# air_qulity_monitor.net
KiCad netlist of a schematic drawn in Altium Designer
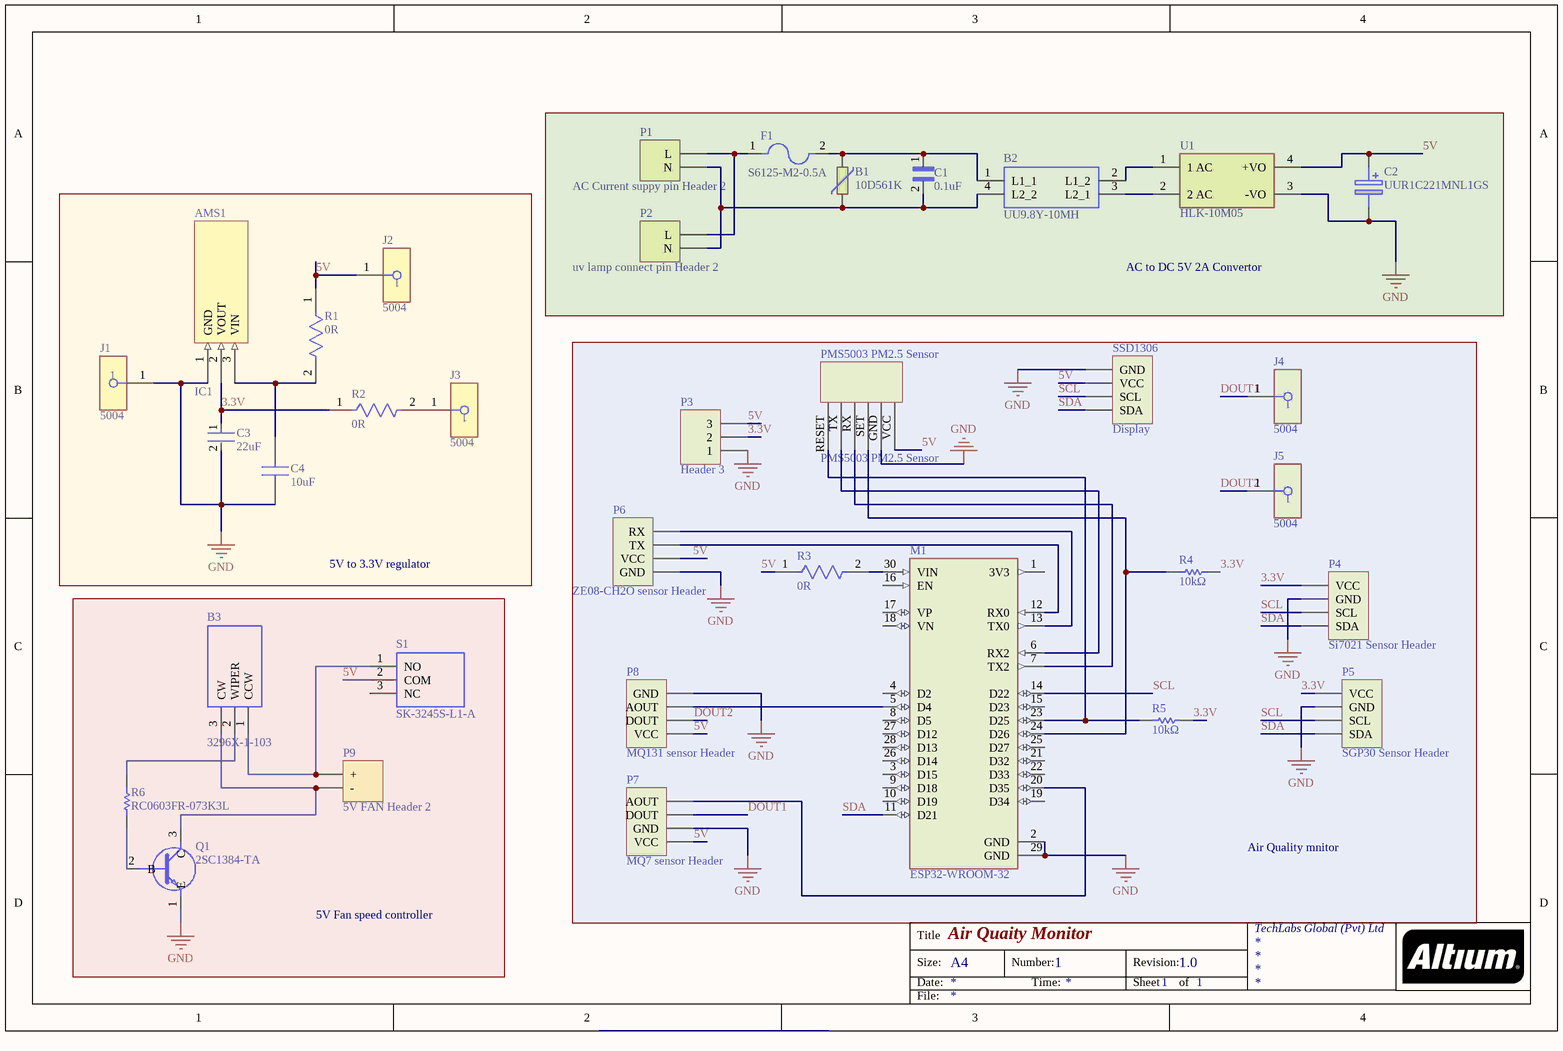
[diagram p0: air qulity monitor.SchDoc]

(export (version "E")
  (design (tool "Eeschema 10.0.6"))
  (components
    (comp (ref "AMS1")
      (value "IC1")
      (footprint "SOT89-150P350X150-3N")
      (fields
        (field (name "MANUFACTURER") "YONGYUTAI")
        (field (name "MFR. PART #") "AMS1117-3.3")
        (field (name "LCSC PART #") "C2904742")
      )
      (libsource (lib "AMS1117-3.3") (part "IC?"))
    )
    (comp (ref "B1")
      (value "10D561K")
      (footprint "10D561K")
      (description "920V 42.3J 180pF@1kHz 460V 350V 504V~616V 2.5kA Plugin Varistors ROHS")
      (fields (field (name "LCSC PART #") "C113236") (field (name "MANUFACTURER") "Hongzhi Elec"))
      (libsource (lib "10D561K") (part "10D561K"))
    )
    (comp (ref "B2")
      (value "UU9.8Y-10MH")
      (footprint "UU98Y10MH")
      (description "Common Mode Chokes / Filters Power Line 10mH @ 1kHz 500mA Through Hole RoHS")
      (libsource (lib "UU9.8Y-10MH") (part "UU9.8Y-10MH"))
    )
    (comp (ref "B3")
      (value "3296X-1-103")
      (footprint "3296X1223LF")
      (description "3296X side adj cermet trimmer,10K 10mm")
      (fields (field (name "MOUSER PART NUMBER") "652-3296X-1-103"))
      (libsource (lib "3296X-1-103") (part "3296X-1-103"))
    )
    (comp (ref "C1")
      (value "0.1uF")
      (footprint "MPX-104K275VAC-C-D2")
      (description "0.1uF ±10% -40℃~+110℃ X2 275VAC Radial Leaded,P=15mm Suppression Capacitors ROHS")
      (fields (field (name "LCSC PART #") "C3249976") (field (name "MANUFACTURER") "CORETONG"))
      (libsource (lib "MPX-104K275VAC-C-D2") (part "MPX-104K275VAC-C-D2"))
    )
    (comp (ref "C2")
      (value "UUR1C221MNL1GS")
      (footprint "CAPAE830X1050N")
      (description "Nichicon 220uF 16V dc Aluminium Electrolytic Capacitor, Surface Mount 8 (Dia.) x 10mm +85C 8mm")
      (fields (field (name "MOUSER PART NUMBER") "647-UUR1C221MNL1GS"))
      (libsource (lib "UUR1C221MNL1GS") (part "UUR1C221MNL1GS"))
    )
    (comp (ref "C3")
      (value "22uF")
      (footprint "FP-GRM219-0_2-0_15-IPC_A")
      (description "Chip Multilayer Ceramic Capacitors for General Purpose, 0805, 22uF, X5R, 15%, 20%, 16V")
      (fields (field (name "MFR. PART #") "GRM219R61C226ME15L") (field (name "LCSC PART #") "C162295"))
      (libsource (lib "Altium Content Vault") (part "b4654b650e69147ec39a6b967a45e02"))
    )
    (comp (ref "C4")
      (value "10uF")
      (footprint "CAPC1005X70N")
      (description "6.3V 10uF X5R ±20% 0402 Multilayer Ceramic Capacitors MLCC - SMD/SMT ROHS")
      (fields
        (field (name "MANUFACTURER") "Samsung Electro-Mechanics")
        (field (name "MFR. PART #") "CL05A106MQ5NUNC")
      )
      (libsource (lib "CL05A106MQ5NUNC") (part "CL05A106MQ5NUNC"))
    )
    (comp (ref "F1")
      (value "S6125-M2-0.5A")
      (footprint "CAPC6125X25N")
      (description "SMD Fuses ROHS")
      (fields (field (name "LCSC PART #") "C845172") (field (name "MANUFACTURER") "SART(Nanjing Sart Tech)"))
      (libsource (lib "S6125-M2-0.5A") (part "S6125-M2-0.5A"))
    )
    (comp (ref "J1")
      (value "5004")
      (footprint "FP-5004-MFG")
      (description "PC TEST POINT MINIATURE YELLOW")
      (fields (field (name "MANUFACTURER") "Keystone") (field (name "LCSC PART #") "C2906762"))
      (libsource (lib "") (part "98815daf2f2c152b0c43f5ab9800df6_1"))
    )
    (comp (ref "J2")
      (value "5004")
      (footprint "FP-5004-MFG")
      (description "PC TEST POINT MINIATURE YELLOW")
      (fields (field (name "MANUFACTURER") "Keystone") (field (name "LCSC PART #") "C2906762"))
      (libsource (lib "Altium Content Vault") (part "98815daf2f2c152b0c43f5ab9800df6"))
    )
    (comp (ref "J3")
      (value "5004")
      (footprint "FP-5004-MFG")
      (description "PC TEST POINT MINIATURE YELLOW")
      (fields (field (name "MANUFACTURER") "Keystone") (field (name "LCSC PART #") "C2906762"))
      (libsource (lib "Altium Content Vault") (part "98815daf2f2c152b0c43f5ab9800df6"))
    )
    (comp (ref "J4")
      (value "5004")
      (footprint "FP-5004-MFG")
      (description "PC TEST POINT MINIATURE YELLOW")
      (fields (field (name "MANUFACTURER") "Keystone") (field (name "LCSC PART #") "C2906762"))
      (libsource (lib "Altium Content Vault") (part "98815daf2f2c152b0c43f5ab9800df6"))
    )
    (comp (ref "J5")
      (value "5004")
      (footprint "FP-5004-MFG")
      (description "PC TEST POINT MINIATURE YELLOW")
      (fields (field (name "MANUFACTURER") "Keystone") (field (name "LCSC PART #") "C2906762"))
      (libsource (lib "Altium Content Vault") (part "98815daf2f2c152b0c43f5ab9800df6"))
    )
    (comp (ref "M1")
      (value "ESP32-WROOM-32")
      (footprint "ESP32-DEVKIT-V1")
      (libsource (lib "Modules") (part "ESP32-DEVKIT-V1"))
    )
    (comp (ref "P1")
      (value "AC Current suppy pin Header 2")
      (footprint "HDR1X2")
      (description "Header, 2-Pin")
      (fields (field (name "PUBLISHER") "Altium Limited"))
      (libsource (lib "") (part "Header 2_1"))
    )
    (comp (ref "P2")
      (value "uv lamp connect pin Header 2")
      (footprint "HDR1X2")
      (description "Header, 2-Pin")
      (fields (field (name "PUBLISHER") "Altium Limited"))
      (libsource (lib "") (part "Header 2_1"))
    )
    (comp (ref "P3")
      (value "Header 3")
      (footprint "HDR1X3")
      (description "Header, 3-Pin")
      (fields (field (name "PUBLISHER") "Altium Limited"))
      (libsource (lib "Miscellaneous Connectors") (part "Header 3"))
    )
    (comp (ref "P4")
      (value "Si7021 Sensor Header")
      (footprint "HDR1X4")
      (description "Header, 4-Pin")
      (fields (field (name "PUBLISHER") "Altium Limited"))
      (libsource (lib "") (part "Header 4_2"))
    )
    (comp (ref "P5")
      (value "SGP30 Sensor Header")
      (footprint "HDR1X4")
      (description "Header, 4-Pin")
      (fields (field (name "PUBLISHER") "Altium Limited"))
      (libsource (lib "") (part "Header 4_2"))
    )
    (comp (ref "P6")
      (value "ZE08-CH2O sensor Header")
      (footprint "HDR1X4")
      (description "Header, 4-Pin")
      (fields (field (name "PUBLISHER") "Altium Limited"))
      (libsource (lib "Miscellaneous Connectors") (part "Header 4"))
    )
    (comp (ref "P7")
      (value "MQ7 sensor Header")
      (footprint "HDR1X4")
      (description "Header, 4-Pin")
      (fields (field (name "PUBLISHER") "Altium Limited"))
      (libsource (lib "Miscellaneous Connectors") (part "Header 4"))
    )
    (comp (ref "P8")
      (value "MQ131 sensor Header")
      (footprint "HDR1X4")
      (description "Header, 4-Pin")
      (fields (field (name "PUBLISHER") "Altium Limited"))
      (libsource (lib "Miscellaneous Connectors") (part "Header 4"))
    )
    (comp (ref "P9")
      (value "5V FAN Header 2")
      (footprint "HDR1X2")
      (description "Header, 2-Pin")
      (fields (field (name "PUBLISHER") "Altium Limited"))
      (libsource (lib "Miscellaneous Connectors") (part "Header 2"))
    )
    (comp (ref "PMS5003 PM2.5 Sensor")
      (value "PMS5003 PM2.5 Sensor")
      (footprint "PMS5003 PM2.5 Sensor")
      (libsource (lib "DIY Air Quality Monitor Library") (part "PMS5003 PM2.5 Sensor"))
    )
    (comp (ref "Q1")
      (value "2SC1384-TA")
      (footprint "2SC1384-TA")
      (description "Bipolar Transistors - BJT NPN Si Transistor Epitaxial")
      (fields
        (field (name "MANUFACTURER") "Jiangsu Changjing Electronics Technology Co., Ltd.")
        (field (name "LCSC PART #") "C2910422")
      )
      (libsource (lib "2SC1384-TA") (part "2SC1384-TA"))
    )
    (comp (ref "R1")
      (value "0R")
      (footprint "FP-RC0402-0_4-IPC_A")
      (description "RES SMD 0 OHM JUMPER 1/16W 0402")
      (fields (field (name "MANUFACTURER") "Yageo") (field (name "LCSC PART #") "C106231"))
      (libsource (lib "Altium Content Vault") (part "1029c3af85768c4190bb7ad29bc67b5"))
    )
    (comp (ref "R2")
      (value "0R")
      (footprint "FP-RC0402-0_4-IPC_A")
      (description "RES SMD 0 OHM JUMPER 1/16W 0402")
      (fields (field (name "MANUFACTURER") "Yageo") (field (name "LCSC PART #") "C106231"))
      (libsource (lib "Altium Content Vault") (part "1029c3af85768c4190bb7ad29bc67b5"))
    )
    (comp (ref "R3")
      (value "0R")
      (footprint "FP-RC0402-0_4-IPC_A")
      (description "RES SMD 0 OHM JUMPER 1/16W 0402")
      (fields (field (name "MANUFACTURER") "Yageo") (field (name "LCSC PART #") "C106231"))
      (libsource (lib "Altium Content Vault") (part "1029c3af85768c4190bb7ad29bc67b5"))
    )
    (comp (ref "R4")
      (value "10kΩ")
      (footprint "RESC1005X40X25LL05T10")
      (description "62.5mW 50V ±100ppm/℃ ±1% -55℃~+155℃ 10kΩ 0402 Chip Resistor - Surface Mount ROHS")
      (fields (field (name "MFR. PART #") "RC0402FR-0710KL") (field (name "MANUFACTURER") "Yageo / Phycomp"))
      (libsource (lib "Altium Content Vault") (part "RES"))
    )
    (comp (ref "R5")
      (value "10kΩ")
      (footprint "RESC1005X40X25LL05T10")
      (description "62.5mW 50V ±100ppm/℃ ±1% -55℃~+155℃ 10kΩ 0402 Chip Resistor - Surface Mount ROHS")
      (fields (field (name "MFR. PART #") "RC0402FR-0710KL") (field (name "MANUFACTURER") "Yageo / Phycomp"))
      (libsource (lib "Altium Content Vault") (part "RES"))
    )
    (comp (ref "R6")
      (value "RC0603FR-073K3L")
      (footprint "RESC1608X55X25ML10T15")
      (description "Chip Resistor, 3.3 KOhm, +/- 1%, 0.1 W, -55 to 155 degC, 0603 (1608 Metric), RoHS, Tape and Reel")
      (fields (field (name "MANUFACTURER") "Yageo") (field (name "TOLERANCE") "1%"))
      (libsource (lib "Altium Content Vault") (part "RES-2"))
    )
    (comp (ref "S1")
      (value "SK-3245S-L1-A")
      (footprint "SK3245SL1A")
      (libsource (lib "SK-3245S-L1-A") (part "SK-3245S-L1-A"))
    )
    (comp (ref "SSD1306")
      (value "Display")
      (footprint "HDR1X4")
      (description "Header, 4-Pin")
      (fields (field (name "PUBLISHER") "Altium Limited"))
      (libsource (lib "") (part "Header 4_1"))
    )
    (comp (ref "U1")
      (value "HLK-10M05")
      (footprint "FP-HLK-10M05-MFG")
      (description "10W Ultra-Compact Power Module")
      (libsource (lib "Altium Content Vault") (part "a65b17ccb3a75dffb3c3e849074403b"))
    )
  )
  (nets
    (net (code "1") (name "/3.3V") (class "Default")
      (node (ref "AMS1") (pin "2") (pinfunction "VOUT_2") (pintype "input"))
      (node (ref "C3") (pin "1") (pinfunction "1_1") (pintype "passive"))
      (node (ref "P3") (pin "2") (pinfunction "2_2") (pintype "passive"))
      (node (ref "P4") (pin "1") (pinfunction "VCC_1") (pintype "passive"))
      (node (ref "P5") (pin "1") (pinfunction "VCC_1") (pintype "passive"))
      (node (ref "R2") (pin "1") (pinfunction "1_1") (pintype "passive"))
      (node (ref "R4") (pin "2") (pinfunction "2_2") (pintype "passive"))
      (node (ref "R5") (pin "2") (pinfunction "2_2") (pintype "passive"))
    )
    (net (code "2") (name "/5V") (class "Default")
      (node (ref "C2") (pin "1") (pinfunction "+_1") (pintype "passive"))
      (node (ref "J2") (pin "1") (pinfunction "1_1") (pintype "passive"))
      (node (ref "P3") (pin "3") (pinfunction "3_3") (pintype "passive"))
      (node (ref "P6") (pin "2") (pinfunction "VCC_2") (pintype "passive"))
      (node (ref "P7") (pin "1") (pinfunction "GND_1") (pintype "passive"))
      (node (ref "P8") (pin "1") (pinfunction "GND_1") (pintype "passive"))
      (node (ref "PMS5003 PM2.5 Sensor") (pin "VCC") (pintype "passive"))
      (node (ref "R1") (pin "1") (pinfunction "1_1") (pintype "passive"))
      (node (ref "R3") (pin "1") (pinfunction "1_1") (pintype "passive"))
      (node (ref "S1") (pin "2") (pinfunction "COM_2") (pintype "passive"))
      (node (ref "SSD1306") (pin "2") (pinfunction "VCC_2") (pintype "passive"))
      (node (ref "U1") (pin "4") (pinfunction "+VO_4") (pintype "power_in"))
    )
    (net (code "3") (name "/DOUT1") (class "Default")
      (node (ref "J4") (pin "1") (pinfunction "1_1") (pintype "passive"))
      (node (ref "P7") (pin "3") (pinfunction "TX_3") (pintype "passive"))
    )
    (net (code "4") (name "/DOUT2") (class "Default")
      (node (ref "J5") (pin "1") (pinfunction "1_1") (pintype "passive"))
      (node (ref "P8") (pin "2") (pinfunction "VCC_2") (pintype "passive"))
    )
    (net (code "5") (name "/SCL") (class "Default")
      (node (ref "M1") (pin "14") (pinfunction "D22_14") (pintype "bidirectional"))
      (node (ref "P4") (pin "3") (pinfunction "SCL_3") (pintype "passive"))
      (node (ref "P5") (pin "3") (pinfunction "SCL_3") (pintype "passive"))
      (node (ref "SSD1306") (pin "3") (pinfunction "SCL_3") (pintype "passive"))
    )
    (net (code "6") (name "/SDA") (class "Default")
      (node (ref "M1") (pin "11") (pinfunction "D21_11") (pintype "bidirectional"))
      (node (ref "P4") (pin "4") (pinfunction "SDA_4") (pintype "passive"))
      (node (ref "P5") (pin "4") (pinfunction "SDA_4") (pintype "passive"))
      (node (ref "SSD1306") (pin "4") (pinfunction "SDA_4") (pintype "passive"))
    )
    (net (code "7") (name "GND") (class "Default")
      (node (ref "AMS1") (pin "1") (pinfunction "GND_1") (pintype "input"))
      (node (ref "C2") (pin "2") (pinfunction "-_2") (pintype "passive"))
      (node (ref "C3") (pin "2") (pinfunction "2_2") (pintype "passive"))
      (node (ref "C4") (pin "1") (pinfunction "1_1") (pintype "passive"))
      (node (ref "J1") (pin "1") (pinfunction "1_1") (pintype "passive"))
      (node (ref "M1") (pin "2") (pinfunction "GND_2") (pintype "power_in"))
      (node (ref "M1") (pin "29") (pinfunction "GND_29") (pintype "power_in"))
      (node (ref "P3") (pin "1") (pinfunction "1_1") (pintype "passive"))
      (node (ref "P4") (pin "2") (pinfunction "GND_2") (pintype "passive"))
      (node (ref "P5") (pin "2") (pinfunction "GND_2") (pintype "passive"))
      (node (ref "P6") (pin "1") (pinfunction "GND_1") (pintype "passive"))
      (node (ref "P7") (pin "2") (pinfunction "VCC_2") (pintype "passive"))
      (node (ref "P8") (pin "4") (pinfunction "RX_4") (pintype "passive"))
      (node (ref "PMS5003 PM2.5 Sensor") (pin "GND") (pintype "passive"))
      (node (ref "Q1") (pin "1") (pinfunction "E_1") (pintype "passive"))
      (node (ref "SSD1306") (pin "1") (pinfunction "GND_1") (pintype "passive"))
      (node (ref "U1") (pin "3") (pinfunction "-VO_3") (pintype "power_in"))
    )
    (net (code "8") (name "Net-(AMS1-VIN)") (class "Default")
      (node (ref "AMS1") (pin "3") (pinfunction "VIN_3") (pintype "input"))
      (node (ref "C4") (pin "2") (pinfunction "2_2") (pintype "passive"))
      (node (ref "R1") (pin "2") (pinfunction "2_2") (pintype "passive"))
    )
    (net (code "9") (name "Net-(B2-L1_1)") (class "Default")
      (node (ref "B1") (pin "1") (pinfunction "1_1") (pintype "passive"))
      (node (ref "B2") (pin "1") (pinfunction "L1_1_1") (pintype "passive"))
      (node (ref "C1") (pin "1") (pinfunction "1_1") (pintype "passive"))
      (node (ref "F1") (pin "2") (pinfunction "2_2") (pintype "passive"))
    )
    (net (code "10") (name "Net-(B2-L1_2)") (class "Default")
      (node (ref "B2") (pin "2") (pinfunction "L1_2_2") (pintype "passive"))
      (node (ref "U1") (pin "1") (pinfunction "1_AC_1") (pintype "passive"))
    )
    (net (code "11") (name "Net-(B2-L2_1)") (class "Default")
      (node (ref "B2") (pin "3") (pinfunction "L2_1_3") (pintype "passive"))
      (node (ref "U1") (pin "2") (pinfunction "2_AC_2") (pintype "passive"))
    )
    (net (code "12") (name "Net-(B2-L2_2)") (class "Default")
      (node (ref "B1") (pin "2") (pinfunction "2_2") (pintype "passive"))
      (node (ref "B2") (pin "4") (pinfunction "L2_2_4") (pintype "passive"))
      (node (ref "C1") (pin "2") (pinfunction "2_2") (pintype "passive"))
      (node (ref "P1") (pin "1") (pinfunction "N_1") (pintype "passive"))
      (node (ref "P2") (pin "1") (pinfunction "N_1") (pintype "passive"))
    )
    (net (code "13") (name "Net-(B3-CCW)") (class "Default")
      (node (ref "B3") (pin "1") (pinfunction "CCW_1") (pintype "passive"))
      (node (ref "P9") (pin "1") (pinfunction "+_1") (pintype "passive"))
      (node (ref "S1") (pin "1") (pinfunction "NO_1") (pintype "passive"))
    )
    (net (code "14") (name "Net-(B3-CW)") (class "Default")
      (node (ref "B3") (pin "3") (pinfunction "CW_3") (pintype "passive"))
      (node (ref "P9") (pin "2") (pinfunction "-_2") (pintype "passive"))
      (node (ref "Q1") (pin "3") (pinfunction "C_3") (pintype "passive"))
    )
    (net (code "15") (name "Net-(B3-WIPER)") (class "Default")
      (node (ref "B3") (pin "2") (pinfunction "WIPER_2") (pintype "passive"))
      (node (ref "R6") (pin "2") (pinfunction "2_2") (pintype "passive"))
    )
    (net (code "16") (name "Net-(J3-Pad1)") (class "Default")
      (node (ref "J3") (pin "1") (pinfunction "1_1") (pintype "passive"))
      (node (ref "R2") (pin "2") (pinfunction "2_2") (pintype "passive"))
    )
    (net (code "17") (name "Net-(M1-D4)") (class "Default")
      (node (ref "M1") (pin "5") (pinfunction "D4_5") (pintype "bidirectional"))
      (node (ref "P8") (pin "3") (pinfunction "TX_3") (pintype "passive"))
    )
    (net (code "18") (name "Net-(M1-D25)") (class "Default")
      (node (ref "M1") (pin "23") (pinfunction "D25_23") (pintype "bidirectional"))
      (node (ref "PMS5003 PM2.5 Sensor") (pin "RESET") (pintype "passive"))
      (node (ref "R5") (pin "1") (pinfunction "1_1") (pintype "passive"))
    )
    (net (code "19") (name "Net-(M1-D26)") (class "Default")
      (node (ref "M1") (pin "24") (pinfunction "D26_24") (pintype "bidirectional"))
      (node (ref "PMS5003 PM2.5 Sensor") (pin "SET") (pintype "passive"))
      (node (ref "R4") (pin "1") (pinfunction "1_1") (pintype "passive"))
    )
    (net (code "20") (name "Net-(M1-D35)") (class "Default")
      (node (ref "M1") (pin "20") (pinfunction "D35_20") (pintype "bidirectional"))
      (node (ref "P7") (pin "4") (pinfunction "RX_4") (pintype "passive"))
    )
    (net (code "21") (name "Net-(M1-RX0)") (class "Default")
      (node (ref "M1") (pin "12") (pinfunction "RX0_12") (pintype "input"))
      (node (ref "P6") (pin "3") (pinfunction "TX_3") (pintype "passive"))
    )
    (net (code "22") (name "Net-(M1-RX2)") (class "Default")
      (node (ref "M1") (pin "6") (pinfunction "RX2_6") (pintype "input"))
      (node (ref "PMS5003 PM2.5 Sensor") (pin "TX") (pintype "passive"))
    )
    (net (code "23") (name "Net-(M1-TX0)") (class "Default")
      (node (ref "M1") (pin "13") (pinfunction "TX0_13") (pintype "output"))
      (node (ref "P6") (pin "4") (pinfunction "RX_4") (pintype "passive"))
    )
    (net (code "24") (name "Net-(M1-TX2)") (class "Default")
      (node (ref "M1") (pin "7") (pinfunction "TX2_7") (pintype "output"))
      (node (ref "PMS5003 PM2.5 Sensor") (pin "RX") (pintype "passive"))
    )
    (net (code "25") (name "Net-(M1-VIN)") (class "Default")
      (node (ref "M1") (pin "30") (pinfunction "VIN_30") (pintype "input"))
      (node (ref "R3") (pin "2") (pinfunction "2_2") (pintype "passive"))
    )
    (net (code "26") (name "Net-(P1-L)") (class "Default")
      (node (ref "F1") (pin "1") (pinfunction "1_1") (pintype "passive"))
      (node (ref "P1") (pin "2") (pinfunction "L_2") (pintype "passive"))
      (node (ref "P2") (pin "2") (pinfunction "L_2") (pintype "passive"))
    )
    (net (code "27") (name "Net-(Q1-B)") (class "Default")
      (node (ref "Q1") (pin "2") (pinfunction "B_2") (pintype "passive"))
      (node (ref "R6") (pin "1") (pinfunction "1_1") (pintype "passive"))
    )
    (net (code "28") (name "unconnected-(M1-3V3-Pad1)") (class "Default")
      (node (ref "M1") (pin "1") (pinfunction "3V3_1") (pintype "output"))
    )
    (net (code "29") (name "unconnected-(M1-D2-Pad4)") (class "Default")
      (node (ref "M1") (pin "4") (pinfunction "D2_4") (pintype "bidirectional"))
    )
    (net (code "30") (name "unconnected-(M1-D5-Pad8)") (class "Default")
      (node (ref "M1") (pin "8") (pinfunction "D5_8") (pintype "bidirectional"))
    )
    (net (code "31") (name "unconnected-(M1-D12-Pad27)") (class "Default")
      (node (ref "M1") (pin "27") (pinfunction "D12_27") (pintype "bidirectional"))
    )
    (net (code "32") (name "unconnected-(M1-D13-Pad28)") (class "Default")
      (node (ref "M1") (pin "28") (pinfunction "D13_28") (pintype "bidirectional"))
    )
    (net (code "33") (name "unconnected-(M1-D14-Pad26)") (class "Default")
      (node (ref "M1") (pin "26") (pinfunction "D14_26") (pintype "bidirectional"))
    )
    (net (code "34") (name "unconnected-(M1-D15-Pad3)") (class "Default")
      (node (ref "M1") (pin "3") (pinfunction "D15_3") (pintype "bidirectional"))
    )
    (net (code "35") (name "unconnected-(M1-D18-Pad9)") (class "Default")
      (node (ref "M1") (pin "9") (pinfunction "D18_9") (pintype "bidirectional"))
    )
    (net (code "36") (name "unconnected-(M1-D19-Pad10)") (class "Default")
      (node (ref "M1") (pin "10") (pinfunction "D19_10") (pintype "bidirectional"))
    )
    (net (code "37") (name "unconnected-(M1-D23-Pad15)") (class "Default")
      (node (ref "M1") (pin "15") (pinfunction "D23_15") (pintype "bidirectional"))
    )
    (net (code "38") (name "unconnected-(M1-D27-Pad25)") (class "Default")
      (node (ref "M1") (pin "25") (pinfunction "D27_25") (pintype "bidirectional"))
    )
    (net (code "39") (name "unconnected-(M1-D32-Pad21)") (class "Default")
      (node (ref "M1") (pin "21") (pinfunction "D32_21") (pintype "bidirectional"))
    )
    (net (code "40") (name "unconnected-(M1-D33-Pad22)") (class "Default")
      (node (ref "M1") (pin "22") (pinfunction "D33_22") (pintype "bidirectional"))
    )
    (net (code "41") (name "unconnected-(M1-D34-Pad19)") (class "Default")
      (node (ref "M1") (pin "19") (pinfunction "D34_19") (pintype "bidirectional"))
    )
    (net (code "42") (name "unconnected-(M1-EN-Pad16)") (class "Default")
      (node (ref "M1") (pin "16") (pinfunction "EN_16") (pintype "input"))
    )
    (net (code "43") (name "unconnected-(M1-VN-Pad18)") (class "Default")
      (node (ref "M1") (pin "18") (pinfunction "VN_18") (pintype "bidirectional"))
    )
    (net (code "44") (name "unconnected-(M1-VP-Pad17)") (class "Default")
      (node (ref "M1") (pin "17") (pinfunction "VP_17") (pintype "bidirectional"))
    )
    (net (code "45") (name "unconnected-(S1-NC-Pad3)") (class "Default")
      (node (ref "S1") (pin "3") (pinfunction "NC_3") (pintype "passive"))
    )
  )
)
